# Schematic.net
KiCad netlist of a schematic drawn in Altium Designer
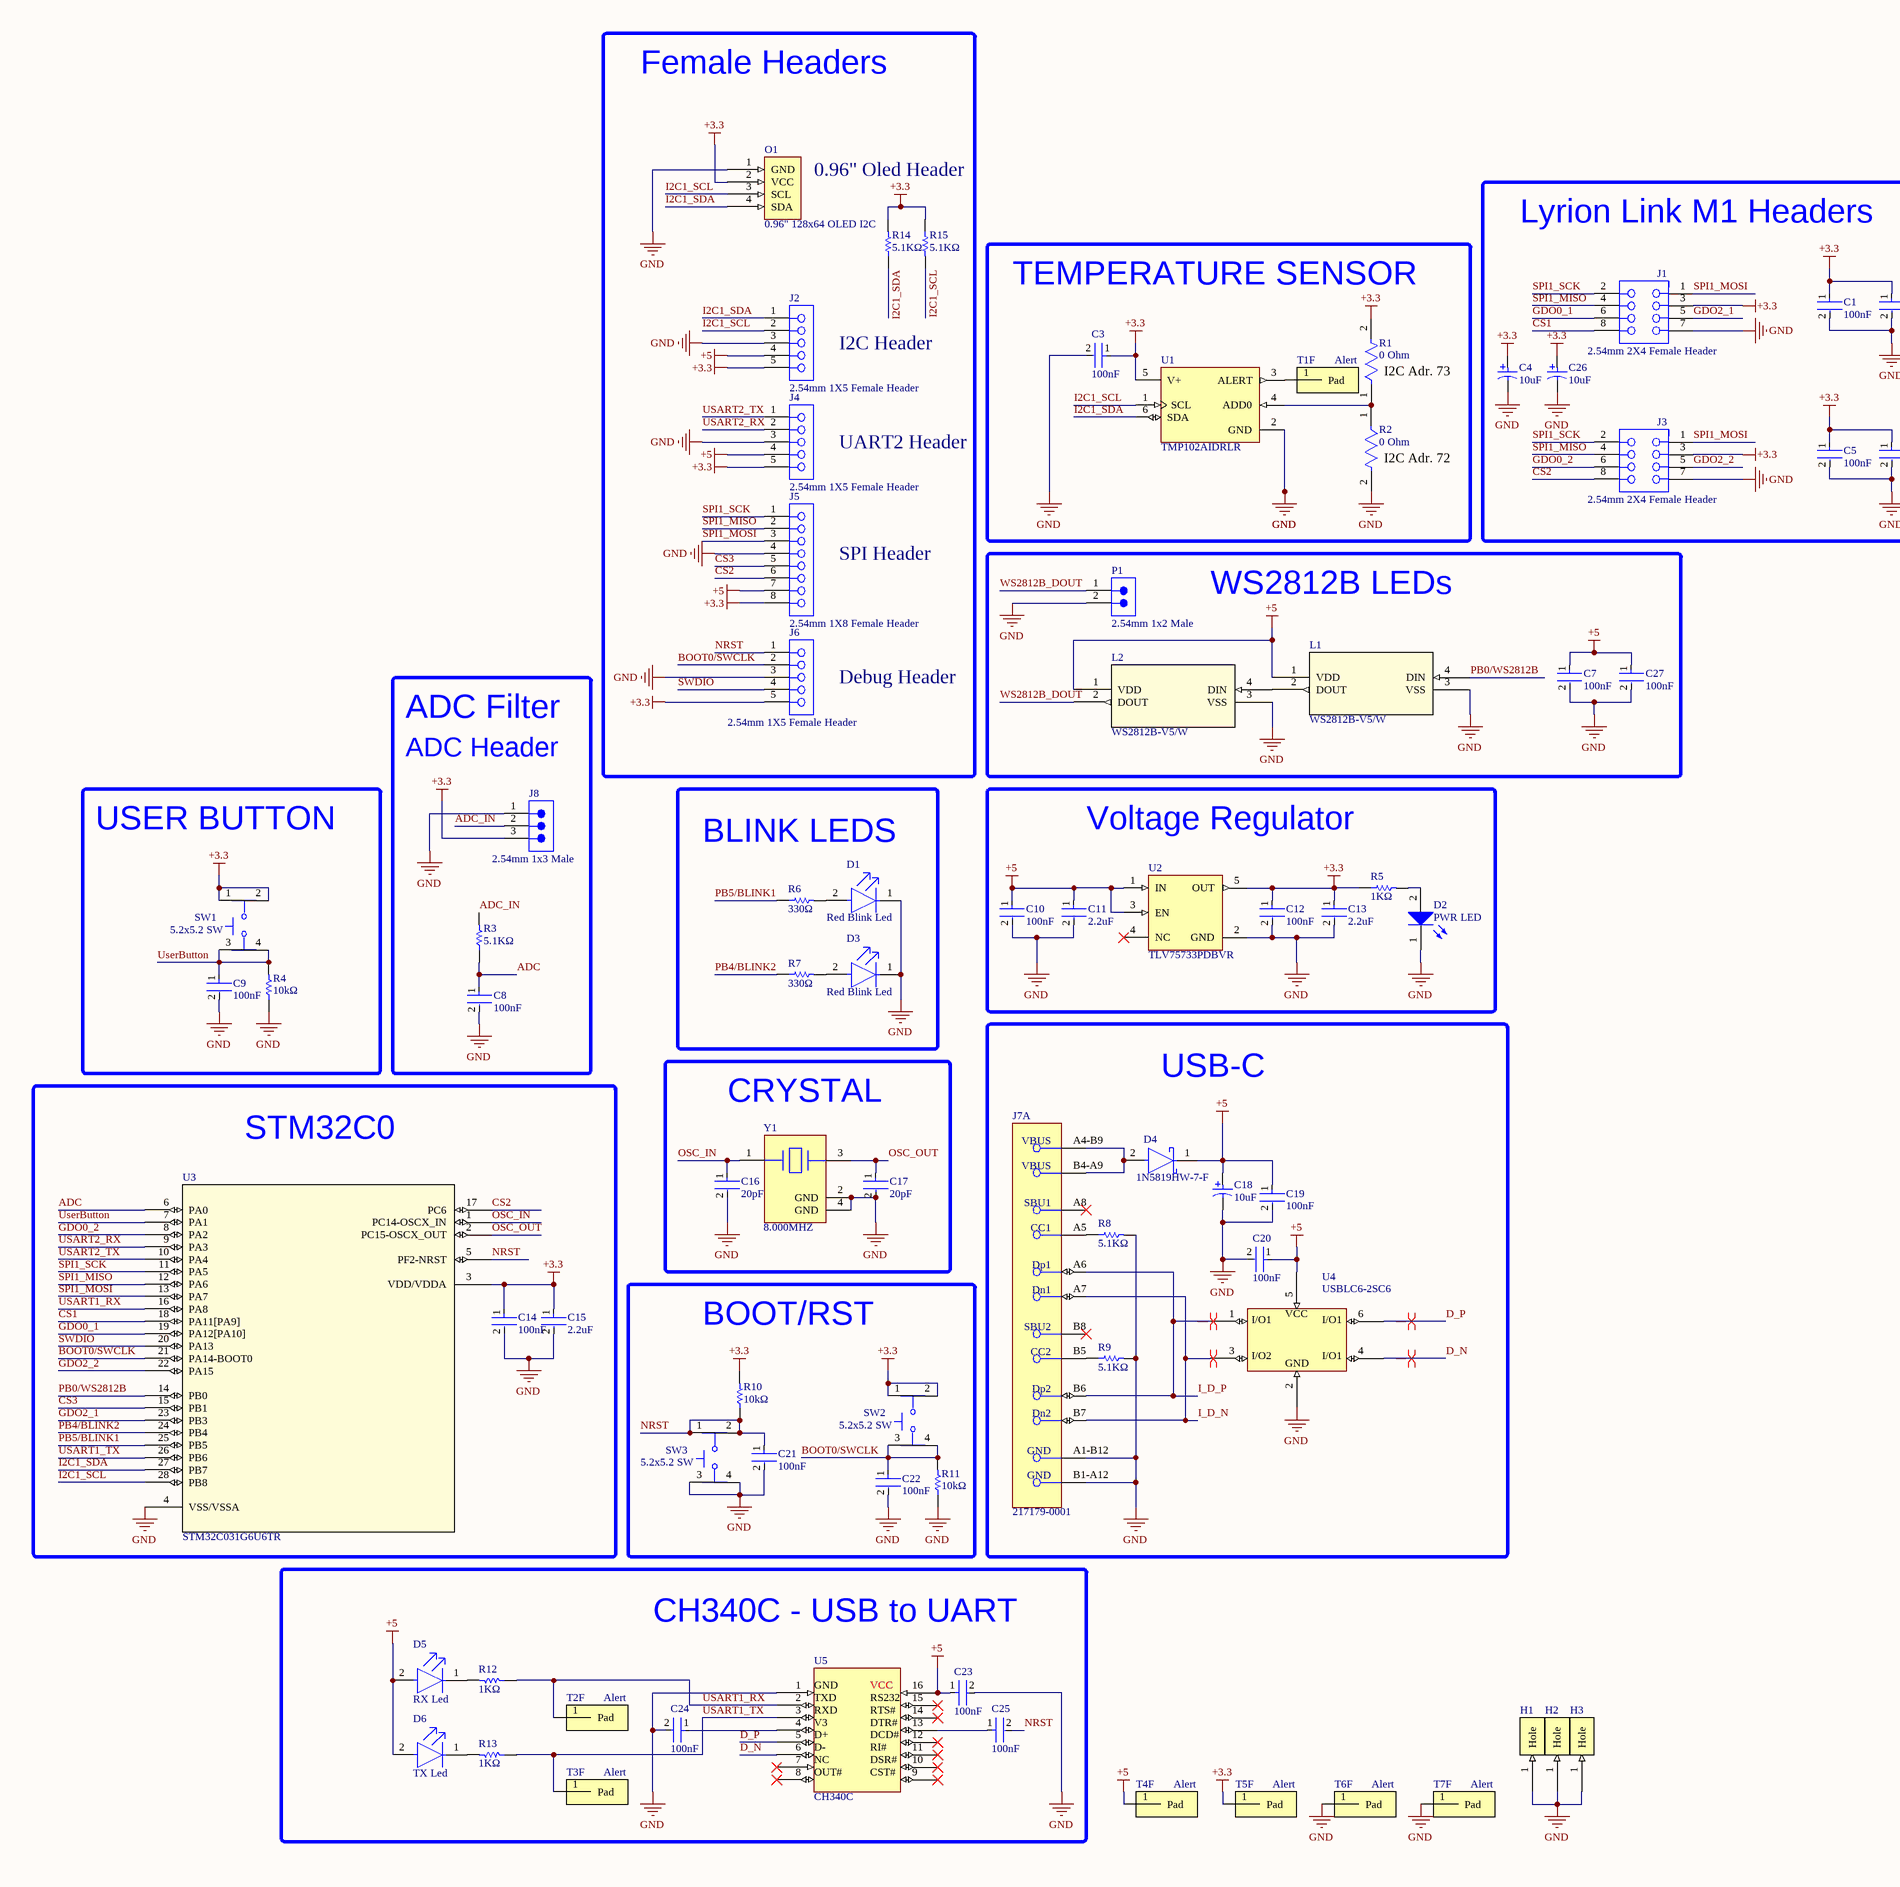
[diagram p0: Schematic.SchDoc, left]
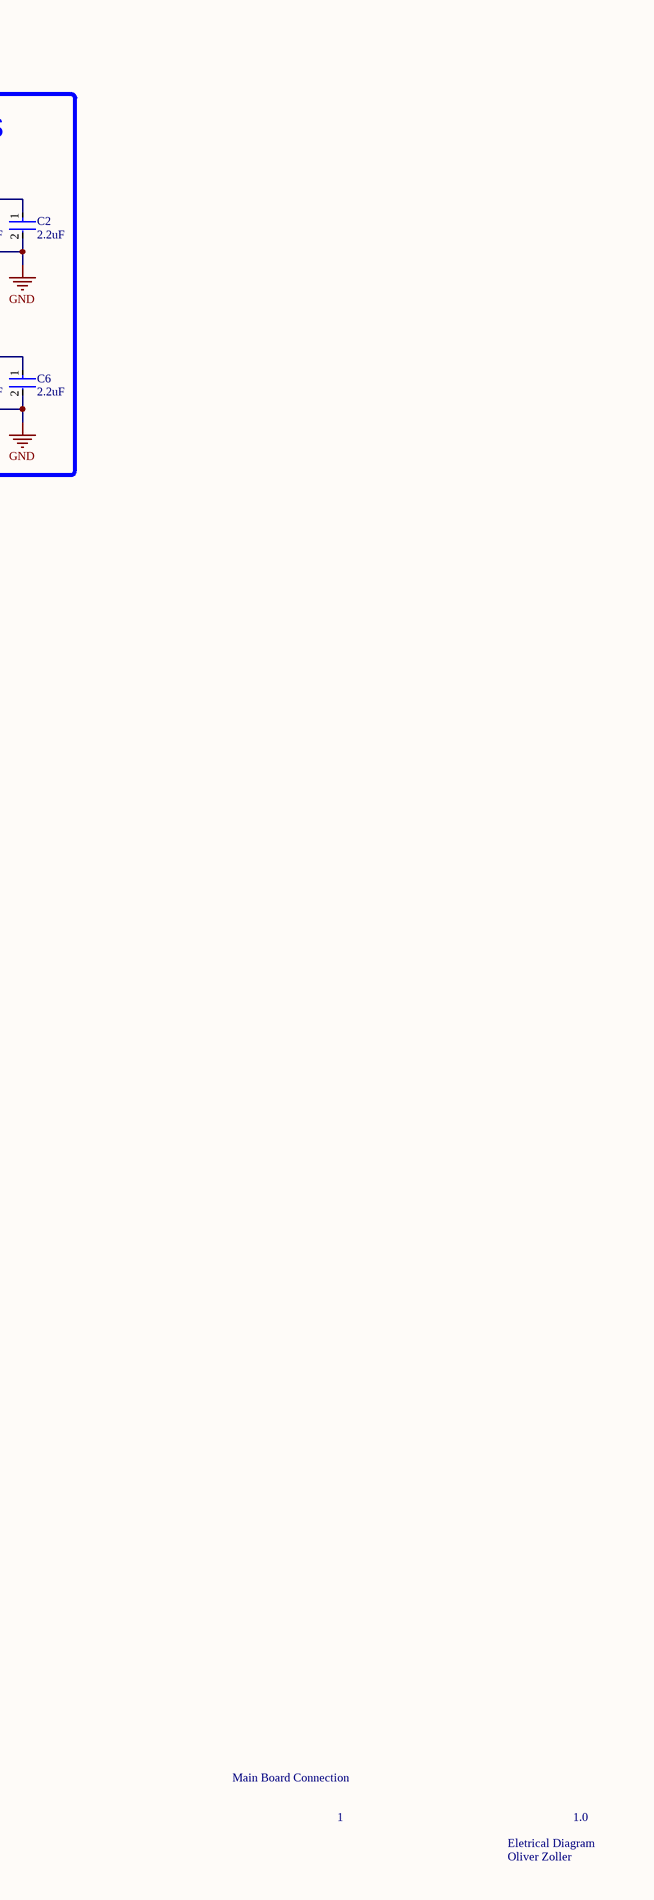
[diagram p1: Schematic.SchDoc, right]

(export (version "E")
  (design (tool "Eeschema 10.0.6"))
  (components
    (comp (ref "C1")
      (value "100nF")
      (footprint "FP-CC0603-DA-IPC_B")
      (description "100nF 0603 10% 50V")
      (fields (field (name "VOLTAGE") "50V") (field (name "TOLERANCE") "10%"))
      (libsource (lib "Main") (part "11868f565c42a9108669ba33697ecf6"))
    )
    (comp (ref "C2")
      (value "2.2uF")
      (footprint "FP-CL10-IPC_B")
      (description "2.2uF 0603 10% 16V")
      (fields (field (name "TOLERANCE") "10%") (field (name "VOLTAGE") "16V"))
      (libsource (lib "Main") (part "b4654b650e69147ec39a6b967a45e02"))
    )
    (comp (ref "C3")
      (value "100nF")
      (footprint "FP-CC0603-DA-IPC_B")
      (description "100nF 0603 10% 50V")
      (fields (field (name "VOLTAGE") "50V") (field (name "TOLERANCE") "10%"))
      (libsource (lib "Main") (part "11868f565c42a9108669ba33697ecf6"))
    )
    (comp (ref "C4")
      (value "10uF")
      (footprint "KEMT-A-3216-18-2_L")
      (description "10uF 0603 10%")
      (fields (field (name "VOLTAGE") "10V") (field (name "TOLERANCE") "10%"))
      (libsource (lib "Main") (part "CAP-P-2"))
    )
    (comp (ref "C5")
      (value "100nF")
      (footprint "FP-CC0603-DA-IPC_B")
      (description "100nF 0603 10% 50V")
      (fields (field (name "VOLTAGE") "50V") (field (name "TOLERANCE") "10%"))
      (libsource (lib "Main") (part "11868f565c42a9108669ba33697ecf6"))
    )
    (comp (ref "C6")
      (value "2.2uF")
      (footprint "FP-CL10-IPC_B")
      (description "2.2uF 0603 10% 16V")
      (fields (field (name "TOLERANCE") "10%") (field (name "VOLTAGE") "16V"))
      (libsource (lib "Main") (part "b4654b650e69147ec39a6b967a45e02"))
    )
    (comp (ref "C7")
      (value "100nF")
      (footprint "FP-CC0603-DA-IPC_B")
      (description "100nF 0603 10% 50V")
      (fields (field (name "VOLTAGE") "50V") (field (name "TOLERANCE") "10%"))
      (libsource (lib "Main") (part "11868f565c42a9108669ba33697ecf6"))
    )
    (comp (ref "C8")
      (value "100nF")
      (footprint "FP-CC0603-DA-IPC_B")
      (description "100nF 0603 10% 50V")
      (fields (field (name "VOLTAGE") "50V") (field (name "TOLERANCE") "10%"))
      (libsource (lib "Main") (part "11868f565c42a9108669ba33697ecf6"))
    )
    (comp (ref "C9")
      (value "100nF")
      (footprint "FP-CC0603-DA-IPC_B")
      (description "100nF 0603 10% 50V")
      (fields (field (name "VOLTAGE") "50V") (field (name "TOLERANCE") "10%"))
      (libsource (lib "Main") (part "11868f565c42a9108669ba33697ecf6"))
    )
    (comp (ref "C10")
      (value "100nF")
      (footprint "FP-CC0603-DA-IPC_B")
      (description "100nF 0603 10% 50V")
      (fields (field (name "VOLTAGE") "50V") (field (name "TOLERANCE") "10%"))
      (libsource (lib "Main") (part "11868f565c42a9108669ba33697ecf6"))
    )
    (comp (ref "C11")
      (value "2.2uF")
      (footprint "FP-CL10-IPC_B")
      (description "2.2uF 0603 10% 16V")
      (fields (field (name "TOLERANCE") "10%") (field (name "VOLTAGE") "16V"))
      (libsource (lib "Main") (part "b4654b650e69147ec39a6b967a45e02"))
    )
    (comp (ref "C12")
      (value "100nF")
      (footprint "FP-CC0603-DA-IPC_B")
      (description "100nF 0603 10% 50V")
      (fields (field (name "VOLTAGE") "50V") (field (name "TOLERANCE") "10%"))
      (libsource (lib "Main") (part "11868f565c42a9108669ba33697ecf6"))
    )
    (comp (ref "C13")
      (value "2.2uF")
      (footprint "FP-CL10-IPC_B")
      (description "2.2uF 0603 10% 16V")
      (fields (field (name "TOLERANCE") "10%") (field (name "VOLTAGE") "16V"))
      (libsource (lib "Main") (part "b4654b650e69147ec39a6b967a45e02"))
    )
    (comp (ref "C14")
      (value "100nF")
      (footprint "FP-CC0603-DA-IPC_B")
      (description "100nF 0603 10% 50V")
      (fields (field (name "VOLTAGE") "50V") (field (name "TOLERANCE") "10%"))
      (libsource (lib "Main") (part "11868f565c42a9108669ba33697ecf6"))
    )
    (comp (ref "C15")
      (value "2.2uF")
      (footprint "FP-CL10-IPC_B")
      (description "2.2uF 0603 10% 16V")
      (fields (field (name "TOLERANCE") "10%") (field (name "VOLTAGE") "16V"))
      (libsource (lib "Main") (part "b4654b650e69147ec39a6b967a45e02"))
    )
    (comp (ref "C16")
      (value "20pF")
      (footprint "FP-CC0603-0_9-IPC_A")
      (description "20pF 0603 5% 50V")
      (fields (field (name "TOLERANCE") "5%"))
      (libsource (lib "Main") (part "b4654b650e69147ec39a6b967a45e02"))
    )
    (comp (ref "C17")
      (value "20pF")
      (footprint "FP-CC0603-0_9-IPC_A")
      (description "20pF 0603 5% 50V")
      (fields (field (name "TOLERANCE") "5%"))
      (libsource (lib "Main") (part "b4654b650e69147ec39a6b967a45e02"))
    )
    (comp (ref "C18")
      (value "10uF")
      (footprint "KEMT-A-3216-18-2_L")
      (description "10uF 0603 10%")
      (fields (field (name "VOLTAGE") "10V") (field (name "TOLERANCE") "10%"))
      (libsource (lib "Main") (part "CAP-P-2"))
    )
    (comp (ref "C19")
      (value "100nF")
      (footprint "FP-CC0603-DA-IPC_B")
      (description "100nF 0603 10% 50V")
      (fields (field (name "VOLTAGE") "50V") (field (name "TOLERANCE") "10%"))
      (libsource (lib "Main") (part "11868f565c42a9108669ba33697ecf6"))
    )
    (comp (ref "C20")
      (value "100nF")
      (footprint "FP-CC0603-DA-IPC_B")
      (description "100nF 0603 10% 50V")
      (fields (field (name "VOLTAGE") "50V") (field (name "TOLERANCE") "10%"))
      (libsource (lib "Main") (part "11868f565c42a9108669ba33697ecf6"))
    )
    (comp (ref "C21")
      (value "100nF")
      (footprint "FP-CC0603-DA-IPC_B")
      (description "100nF 0603 10% 50V")
      (fields (field (name "VOLTAGE") "50V") (field (name "TOLERANCE") "10%"))
      (libsource (lib "Main") (part "11868f565c42a9108669ba33697ecf6"))
    )
    (comp (ref "C22")
      (value "100nF")
      (footprint "FP-CC0603-DA-IPC_B")
      (description "100nF 0603 10% 50V")
      (fields (field (name "VOLTAGE") "50V") (field (name "TOLERANCE") "10%"))
      (libsource (lib "Main") (part "11868f565c42a9108669ba33697ecf6"))
    )
    (comp (ref "C23")
      (value "100nF")
      (footprint "FP-CC0603-DA-IPC_B")
      (description "100nF 0603 10% 50V")
      (fields (field (name "VOLTAGE") "50V") (field (name "TOLERANCE") "10%"))
      (libsource (lib "Main") (part "11868f565c42a9108669ba33697ecf6"))
    )
    (comp (ref "C24")
      (value "100nF")
      (footprint "FP-CC0603-DA-IPC_B")
      (description "100nF 0603 10% 50V")
      (fields (field (name "VOLTAGE") "50V") (field (name "TOLERANCE") "10%"))
      (libsource (lib "Main") (part "11868f565c42a9108669ba33697ecf6"))
    )
    (comp (ref "C25")
      (value "100nF")
      (footprint "FP-CC0603-DA-IPC_B")
      (description "100nF 0603 10% 50V")
      (fields (field (name "VOLTAGE") "50V") (field (name "TOLERANCE") "10%"))
      (libsource (lib "Main") (part "11868f565c42a9108669ba33697ecf6"))
    )
    (comp (ref "C26")
      (value "10uF")
      (footprint "KEMT-A-3216-18-2_L")
      (description "10uF 0603 10%")
      (fields (field (name "VOLTAGE") "10V") (field (name "TOLERANCE") "10%"))
      (libsource (lib "Main") (part "CAP-P-2"))
    )
    (comp (ref "C27")
      (value "100nF")
      (footprint "FP-CC0603-DA-IPC_B")
      (description "100nF 0603 10% 50V")
      (fields (field (name "VOLTAGE") "50V") (field (name "TOLERANCE") "10%"))
      (libsource (lib "Main") (part "11868f565c42a9108669ba33697ecf6"))
    )
    (comp (ref "D1")
      (value "Red Blink Led")
      (footprint "FP-LTST-C190KRKT-MFG")
      (description "LED red 0603 wavelength 631nm light intensity 18~180mcd Front Mounting")
      (fields (field (name "TOLERANCE") "20%"))
      (libsource (lib "Main") (part "8706943c75ba83719d021d2fdc84c58"))
    )
    (comp (ref "D2")
      (value "PWR LED")
      (footprint "WL-SMCW_0603_150060xx75000")
      (description "WL-SMCW SMT Mono-Color Chip LED Waterclear")
      (libsource (lib "Main") (part "LED_Blue_2A-1K"))
    )
    (comp (ref "D3")
      (value "Red Blink Led")
      (footprint "FP-LTST-C190KRKT-MFG")
      (description "LED red 0603 wavelength 631nm light intensity 18~180mcd Front Mounting")
      (fields (field (name "TOLERANCE") "20%"))
      (libsource (lib "Main") (part "8706943c75ba83719d021d2fdc84c58"))
    )
    (comp (ref "D4")
      (value "1N5819HW-7-F")
      (footprint "FP-SOD123-IPC_C")
      (description "Schottky Diode SOD-123 40V 1A")
      (libsource (lib "Main") (part "1d6ec82d83fb6aee721767c19dac4b9"))
    )
    (comp (ref "D5")
      (value "RX Led")
      (footprint "FP-LTST-C190KRKT-MFG")
      (description "LED red 0603 wavelength 631nm light intensity 18~180mcd Front Mounting")
      (fields (field (name "TOLERANCE") "20%"))
      (libsource (lib "Main") (part "8706943c75ba83719d021d2fdc84c58"))
    )
    (comp (ref "D6")
      (value "TX Led")
      (footprint "FP-LTST-C190KRKT-MFG")
      (description "LED red 0603 wavelength 631nm light intensity 18~180mcd Front Mounting")
      (fields (field (name "TOLERANCE") "20%"))
      (libsource (lib "Main") (part "8706943c75ba83719d021d2fdc84c58"))
    )
    (comp (ref "H1")
      (value "M3 Mouting hole")
      (footprint "M3 Mouting hole-Footprint-1")
      (description "hole for M3 screw")
      (libsource (lib "Main") (part "M3 Mouting hole-Symbol-1"))
    )
    (comp (ref "H2")
      (value "M3 Mouting hole")
      (footprint "M3 Mouting hole-Footprint-1")
      (description "hole for M3 screw")
      (libsource (lib "Main") (part "M3 Mouting hole-Symbol-1"))
    )
    (comp (ref "H3")
      (value "M3 Mouting hole")
      (footprint "M3 Mouting hole-Footprint-1")
      (description "hole for M3 screw")
      (libsource (lib "Main") (part "M3 Mouting hole-Symbol-1"))
    )
    (comp (ref "J1")
      (value "2.54mm 2X4 Female Header")
      (footprint "61300821821")
      (description "8 Position Header Connector 0.100 (2.54mm) Through Hole Gold")
      (libsource (lib "Main") (part "Header_Female_2R_08P"))
    )
    (comp (ref "J2")
      (value "2.54mm 1X5 Female Header")
      (footprint "61300511821")
      (description "WR-PHD 2.54 mm Socket Header; 5 pins")
      (libsource (lib "Main") (part "Header_Female_1R_05P"))
    )
    (comp (ref "J3")
      (value "2.54mm 2X4 Female Header")
      (footprint "61300821821")
      (description "8 Position Header Connector 0.100 (2.54mm) Through Hole Gold")
      (libsource (lib "Main") (part "Header_Female_2R_08P"))
    )
    (comp (ref "J4")
      (value "2.54mm 1X5 Female Header")
      (footprint "61300511821")
      (description "WR-PHD 2.54 mm Socket Header; 5 pins")
      (libsource (lib "Main") (part "Header_Female_1R_05P"))
    )
    (comp (ref "J5")
      (value "2.54mm 1X8 Female Header")
      (footprint "61300811821")
      (description "Btb Conn, Rcpt, 8Pos, 1Row, 2.54Mm Rohs Compliant: Yes")
      (libsource (lib "Main") (part "Header_Female_1R_08P"))
    )
    (comp (ref "J6")
      (value "2.54mm 1X5 Female Header")
      (footprint "61300511821")
      (description "WR-PHD 2.54 mm Socket Header; 5 pins")
      (libsource (lib "Main") (part "Header_Female_1R_05P"))
    )
    (comp (ref "J7")
      (value "217179-0001")
      (footprint "FP-2171790001-MFG")
      (description "USB-C 16 pin")
      (libsource (lib "Main") (part "8b86497a633d14b3f74642136fc0ce6"))
    )
    (comp (ref "J8")
      (value "2.54mm 1x3 Male")
      (footprint "61300311121")
      (description "WR-PHD Straight Male, PCB Header, Through Hole, 1 Rows, 3 Contacts, 2.54mm Pitch")
      (libsource (lib "Main") (part "Header_Male_1R_03P"))
    )
    (comp (ref "L1")
      (value "WS2812B-V5/W")
      (footprint "WS2812B-V5_W-Footprint-1")
      (description "SMD5050-4P LED Addressable")
      (libsource (lib "Main") (part "WS2812B-V5_W-Symbol-1"))
    )
    (comp (ref "L2")
      (value "WS2812B-V5/W")
      (footprint "WS2812B-V5_W-Footprint-1")
      (description "SMD5050-4P LED Addressable")
      (libsource (lib "Main") (part "WS2812B-V5_W-Symbol-1"))
    )
    (comp (ref "O1")
      (value "0.96\" 128x64 OLED I2C")
      (footprint "0.96\" 128x64 OLED I2C-Footprint-1")
      (description "Display")
      (libsource (lib "Main") (part "0.96{dblquote} 128x64 OLED I2C-Symbol-1"))
    )
    (comp (ref "P1")
      (value "2.54mm 1x2 Male")
      (footprint "61300211121")
      (description "WR-PHD Straight Male, PCB Header, Through Hole, 1 Rows, 2 Contacts, 2.54mm Pitch")
      (libsource (lib "Main") (part "Header_Male_1R_02P"))
    )
    (comp (ref "R1")
      (value "0 Ohm")
      (footprint "FP-RC0603-MFG")
      (description "0 Ohm 0603")
      (fields (field (name "TOLERANCE") "1%"))
      (libsource (lib "Main") (part "1029c3af85768c4190bb7ad29bc67b5"))
    )
    (comp (ref "R2")
      (value "0 Ohm")
      (footprint "FP-RC0603-MFG")
      (description "0 Ohm 0603")
      (fields (field (name "TOLERANCE") "1%"))
      (libsource (lib "Main") (part "1029c3af85768c4190bb7ad29bc67b5"))
    )
    (comp (ref "R3")
      (value "5.1KΩ")
      (footprint "RESC1608X55X25ML10T15")
      (description "5.1KΩ 0603 1% 75V")
      (fields (field (name "TOLERANCE") "1%"))
      (libsource (lib "Main") (part "RES"))
    )
    (comp (ref "R4")
      (value "10kΩ")
      (footprint "RESC1609X50X30ML8T20")
      (description "10kΩ 0603 1% 75V")
      (fields (field (name "TOLERANCE") "1%"))
      (libsource (lib "Main") (part "RES-2"))
    )
    (comp (ref "R5")
      (value "1KΩ")
      (footprint "RESC1608X55X25ML10T15")
      (description "1KΩ 0603 1% 75V")
      (fields (field (name "TOLERANCE") "1%"))
      (libsource (lib "Main") (part "RES"))
    )
    (comp (ref "R6")
      (value "330Ω")
      (footprint "RESC1608X55X25LL10T15")
      (description "330Ω 0603 ±1% 75V")
      (fields (field (name "TOLERANCE") "1%"))
      (libsource (lib "Main") (part "RES-2"))
    )
    (comp (ref "R7")
      (value "330Ω")
      (footprint "RESC1608X55X25LL10T15")
      (description "330Ω 0603 ±1% 75V")
      (fields (field (name "TOLERANCE") "1%"))
      (libsource (lib "Main") (part "RES-2"))
    )
    (comp (ref "R8")
      (value "5.1KΩ")
      (footprint "RESC1608X55X25ML10T15")
      (description "5.1KΩ 0603 1% 75V")
      (fields (field (name "TOLERANCE") "1%"))
      (libsource (lib "Main") (part "RES"))
    )
    (comp (ref "R9")
      (value "5.1KΩ")
      (footprint "RESC1608X55X25ML10T15")
      (description "5.1KΩ 0603 1% 75V")
      (fields (field (name "TOLERANCE") "1%"))
      (libsource (lib "Main") (part "RES"))
    )
    (comp (ref "R10")
      (value "10kΩ")
      (footprint "RESC1609X50X30ML8T20")
      (description "10kΩ 0603 1% 75V")
      (fields (field (name "TOLERANCE") "1%"))
      (libsource (lib "Main") (part "RES-2"))
    )
    (comp (ref "R11")
      (value "10kΩ")
      (footprint "RESC1609X50X30ML8T20")
      (description "10kΩ 0603 1% 75V")
      (fields (field (name "TOLERANCE") "1%"))
      (libsource (lib "Main") (part "RES-2"))
    )
    (comp (ref "R12")
      (value "1KΩ")
      (footprint "RESC1608X55X25ML10T15")
      (description "1KΩ 0603 1% 75V")
      (fields (field (name "TOLERANCE") "1%"))
      (libsource (lib "Main") (part "RES"))
    )
    (comp (ref "R13")
      (value "1KΩ")
      (footprint "RESC1608X55X25ML10T15")
      (description "1KΩ 0603 1% 75V")
      (fields (field (name "TOLERANCE") "1%"))
      (libsource (lib "Main") (part "RES"))
    )
    (comp (ref "R14")
      (value "5.1KΩ")
      (footprint "RESC1608X55X25ML10T15")
      (description "5.1KΩ 0603 1% 75V")
      (fields (field (name "TOLERANCE") "1%"))
      (libsource (lib "Main") (part "RES"))
    )
    (comp (ref "R15")
      (value "5.1KΩ")
      (footprint "RESC1608X55X25ML10T15")
      (description "5.1KΩ 0603 1% 75V")
      (fields (field (name "TOLERANCE") "1%"))
      (libsource (lib "Main") (part "RES"))
    )
    (comp (ref "SW1")
      (value "5.2x5.2 SW")
      (footprint "FP-TL3342F450QG-MFG")
      (description "Tactile Switch  5.2x5.2 Round Button")
      (libsource (lib "Main") (part "515be15a89bd7fba83aa4975ec48af4"))
    )
    (comp (ref "SW2")
      (value "5.2x5.2 SW")
      (footprint "FP-TL3342F450QG-MFG")
      (description "Tactile Switch  5.2x5.2 Round Button")
      (libsource (lib "Main") (part "515be15a89bd7fba83aa4975ec48af4"))
    )
    (comp (ref "SW3")
      (value "5.2x5.2 SW")
      (footprint "FP-TL3342F450QG-MFG")
      (description "Tactile Switch  5.2x5.2 Round Button")
      (libsource (lib "Main") (part "515be15a89bd7fba83aa4975ec48af4"))
    )
    (comp (ref "T1")
      (value "Alert")
      (footprint "Test Pad-Footprint-1")
      (description "Pad for probing - soldering")
      (libsource (lib "Main") (part "Test Pad-Symbol-1"))
    )
    (comp (ref "T2")
      (value "Alert")
      (footprint "Test Pad-Footprint-1")
      (description "Pad for probing - soldering")
      (libsource (lib "Main") (part "Test Pad-Symbol-1"))
    )
    (comp (ref "T3")
      (value "Alert")
      (footprint "Test Pad-Footprint-1")
      (description "Pad for probing - soldering")
      (libsource (lib "Main") (part "Test Pad-Symbol-1"))
    )
    (comp (ref "T4")
      (value "Alert")
      (footprint "Test Pad-Footprint-1")
      (description "Pad for probing - soldering")
      (libsource (lib "Main") (part "Test Pad-Symbol-1"))
    )
    (comp (ref "T5")
      (value "Alert")
      (footprint "Test Pad-Footprint-1")
      (description "Pad for probing - soldering")
      (libsource (lib "Main") (part "Test Pad-Symbol-1"))
    )
    (comp (ref "T6")
      (value "Alert")
      (footprint "Test Pad-Footprint-1")
      (description "Pad for probing - soldering")
      (libsource (lib "Main") (part "Test Pad-Symbol-1"))
    )
    (comp (ref "T7")
      (value "Alert")
      (footprint "Test Pad-Footprint-1")
      (description "Pad for probing - soldering")
      (libsource (lib "Main") (part "Test Pad-Symbol-1"))
    )
    (comp (ref "U1")
      (value "TMP102AIDRLR")
      (footprint "FP-DRL0006A-MFG")
      (description "Digital Temperature Sensor -40℃~+125℃ I2C ±0.5℃ 1.4V~3.6V SOT-563 Analog and Digital Outpu")
      (libsource (lib "Main") (part "0dc0cc90889c8b3dc03258d40cf2b82"))
    )
    (comp (ref "U2")
      (value "TLV75733PDBVR")
      (footprint "FP-DBV0005A-MFG")
      (description "LDO 3.3V 1A 5-SOT-23")
      (libsource (lib "Main") (part "0cbbc1df71e5372cce39b1d408f1f92"))
    )
    (comp (ref "U3")
      (value "STM32C031G6U6TR")
      (footprint "UFQFPN-28_STM")
      (fields (field (name "COPYRIGHT") "Copyright (C) 2026 Ultra Librarian. All rights reserved."))
      (libsource (lib "Main") (part "STM32C031G6U6TR"))
    )
    (comp (ref "U4")
      (value "USBLC6-2SC6")
      (footprint "STM-SOT23-6L_V")
      (description "USB ESD SOT-23-6 and Surge Protection (TVS/ESD)")
      (libsource (lib "Main") (part "USBLC6-2SC6-Symbol-1"))
    )
    (comp (ref "U5")
      (value "CH340C")
      (footprint "CH340C-Footprint-1")
      (description "USB to Serial Port chip Transceiver 2Mbps USB 2.0 SOP-16 Interface Controllers RoHS")
      (fields
        (field (name "SOURCE") "https://www.lcsc.com/product-detail/C84681.html?spm=wm.gwc.xh.55.cbm___wm.sy.ssl.gwc&lcsc_vid=QQVdUgADR1gPUVVXRVZXVQJRRVdbBFZWEwdaVgBXQwAxVlNRTlBZUFFRRlZYUTtW")
      )
      (libsource (lib "Main") (part "CH340C"))
    )
    (comp (ref "Y1")
      (value "8.000MHZ")
      (footprint "FP-ABM3B-MFG")
      (description "Crystal 8MHz ±10ppm SMD5032-4P 20pF")
      (fields (field (name "TOLERANCE") "0.002%"))
      (libsource (lib "Main") (part "48e526d86b7f2615d98721063c72f49"))
    )
  )
  (nets
    (net (code "1") (name "+3.3") (class "Default")
      (node (ref "C1") (pin "1") (pinfunction "1_1") (pintype "passive"))
      (node (ref "C12") (pin "1") (pinfunction "1_1") (pintype "passive"))
      (node (ref "C13") (pin "1") (pinfunction "1_1") (pintype "passive"))
      (node (ref "C14") (pin "1") (pinfunction "1_1") (pintype "passive"))
      (node (ref "C15") (pin "1") (pinfunction "1_1") (pintype "passive"))
      (node (ref "C2") (pin "1") (pinfunction "1_1") (pintype "passive"))
      (node (ref "C26") (pin "1") (pinfunction "1_1") (pintype "passive"))
      (node (ref "C3") (pin "1") (pinfunction "1_1") (pintype "passive"))
      (node (ref "C4") (pin "1") (pinfunction "1_1") (pintype "passive"))
      (node (ref "C5") (pin "1") (pinfunction "1_1") (pintype "passive"))
      (node (ref "C6") (pin "1") (pinfunction "1_1") (pintype "passive"))
      (node (ref "J1") (pin "3") (pinfunction "3_3") (pintype "passive"))
      (node (ref "J2") (pin "5") (pinfunction "5_5") (pintype "passive"))
      (node (ref "J3") (pin "3") (pinfunction "3_3") (pintype "passive"))
      (node (ref "J4") (pin "5") (pinfunction "5_5") (pintype "passive"))
      (node (ref "J5") (pin "8") (pinfunction "8_8") (pintype "passive"))
      (node (ref "J6") (pin "5") (pinfunction "5_5") (pintype "passive"))
      (node (ref "J8") (pin "3") (pinfunction "3_3") (pintype "passive"))
      (node (ref "O1") (pin "2") (pinfunction "VCC_2") (pintype "input"))
      (node (ref "R1") (pin "2") (pinfunction "2_2") (pintype "passive"))
      (node (ref "R10") (pin "2") (pinfunction "2_2") (pintype "passive"))
      (node (ref "R14") (pin "2") (pinfunction "2_2") (pintype "passive"))
      (node (ref "R15") (pin "1") (pinfunction "1_1") (pintype "passive"))
      (node (ref "R5") (pin "1") (pinfunction "1_1") (pintype "passive"))
      (node (ref "SW1") (pin "1") (pinfunction "1_1") (pintype "passive"))
      (node (ref "SW1") (pin "2") (pinfunction "2_2") (pintype "passive"))
      (node (ref "SW2") (pin "1") (pinfunction "1_1") (pintype "passive"))
      (node (ref "SW2") (pin "2") (pinfunction "2_2") (pintype "passive"))
      (node (ref "T5") (pin "1") (pinfunction "Pad_1") (pintype "passive"))
      (node (ref "U1") (pin "5") (pinfunction "V+_5") (pintype "power_in"))
      (node (ref "U2") (pin "5") (pinfunction "OUT_5") (pintype "output"))
      (node (ref "U3") (pin "3") (pinfunction "VDD/VDDA_3") (pintype "power_in"))
    )
    (net (code "2") (name "+5") (class "Default")
      (node (ref "C10") (pin "1") (pinfunction "1_1") (pintype "passive"))
      (node (ref "C11") (pin "1") (pinfunction "1_1") (pintype "passive"))
      (node (ref "C18") (pin "1") (pinfunction "1_1") (pintype "passive"))
      (node (ref "C19") (pin "1") (pinfunction "1_1") (pintype "passive"))
      (node (ref "C20") (pin "1") (pinfunction "1_1") (pintype "passive"))
      (node (ref "C23") (pin "1") (pinfunction "1_1") (pintype "passive"))
      (node (ref "C27") (pin "1") (pinfunction "1_1") (pintype "passive"))
      (node (ref "C7") (pin "1") (pinfunction "1_1") (pintype "passive"))
      (node (ref "D4") (pin "1") (pinfunction "C_1") (pintype "passive"))
      (node (ref "D5") (pin "2") (pinfunction "A_2") (pintype "passive"))
      (node (ref "D6") (pin "2") (pinfunction "A_2") (pintype "passive"))
      (node (ref "J2") (pin "4") (pinfunction "4_4") (pintype "passive"))
      (node (ref "J4") (pin "4") (pinfunction "4_4") (pintype "passive"))
      (node (ref "J5") (pin "7") (pinfunction "7_7") (pintype "passive"))
      (node (ref "L1") (pin "1") (pinfunction "VDD_1") (pintype "power_in"))
      (node (ref "L2") (pin "1") (pinfunction "VDD_1") (pintype "power_in"))
      (node (ref "T4") (pin "1") (pinfunction "Pad_1") (pintype "passive"))
      (node (ref "U2") (pin "1") (pinfunction "IN_1") (pintype "input"))
      (node (ref "U2") (pin "3") (pinfunction "EN_3") (pintype "input"))
      (node (ref "U4") (pin "5") (pintype "input"))
      (node (ref "U5") (pin "16") (pintype "input"))
    )
    (net (code "3") (name "/ADC") (class "Default")
      (node (ref "C8") (pin "1") (pinfunction "1_1") (pintype "passive"))
      (node (ref "R3") (pin "1") (pinfunction "1_1") (pintype "passive"))
      (node (ref "U3") (pin "6") (pinfunction "PA0_6") (pintype "bidirectional"))
    )
    (net (code "4") (name "/ADC_IN") (class "Default")
      (node (ref "J8") (pin "2") (pinfunction "2_2") (pintype "passive"))
      (node (ref "R3") (pin "2") (pinfunction "2_2") (pintype "passive"))
    )
    (net (code "5") (name "/BOOT0{slash}SWCLK") (class "Default")
      (node (ref "C22") (pin "1") (pinfunction "1_1") (pintype "passive"))
      (node (ref "J6") (pin "2") (pinfunction "2_2") (pintype "passive"))
      (node (ref "R11") (pin "2") (pinfunction "2_2") (pintype "passive"))
      (node (ref "SW2") (pin "3") (pinfunction "3_3") (pintype "passive"))
      (node (ref "SW2") (pin "4") (pinfunction "4_4") (pintype "passive"))
      (node (ref "U3") (pin "21") (pinfunction "PA14-BOOT0_21") (pintype "bidirectional"))
    )
    (net (code "6") (name "/CS1") (class "Default")
      (node (ref "J1") (pin "8") (pinfunction "8_8") (pintype "passive"))
      (node (ref "U3") (pin "18") (pinfunction "PA11[PA9]_18") (pintype "bidirectional"))
    )
    (net (code "7") (name "/CS2") (class "Default")
      (node (ref "J3") (pin "8") (pinfunction "8_8") (pintype "passive"))
      (node (ref "J5") (pin "6") (pinfunction "6_6") (pintype "passive"))
      (node (ref "U3") (pin "17") (pinfunction "PC6_17") (pintype "bidirectional"))
    )
    (net (code "8") (name "/CS3") (class "Default")
      (node (ref "J5") (pin "5") (pinfunction "5_5") (pintype "passive"))
      (node (ref "U3") (pin "15") (pinfunction "PB1_15") (pintype "bidirectional"))
    )
    (net (code "9") (name "/D_N") (class "Default")
      (node (ref "U4") (pin "4") (pintype "bidirectional"))
      (node (ref "U5") (pin "6") (pintype "bidirectional"))
    )
    (net (code "10") (name "/D_P") (class "Default")
      (node (ref "U4") (pin "6") (pintype "bidirectional"))
      (node (ref "U5") (pin "5") (pintype "bidirectional"))
    )
    (net (code "11") (name "/GDO0_1") (class "Default")
      (node (ref "J1") (pin "6") (pinfunction "6_6") (pintype "passive"))
      (node (ref "U3") (pin "19") (pinfunction "PA12[PA10]_19") (pintype "bidirectional"))
    )
    (net (code "12") (name "/GDO0_2") (class "Default")
      (node (ref "J3") (pin "6") (pinfunction "6_6") (pintype "passive"))
      (node (ref "U3") (pin "8") (pinfunction "PA2_8") (pintype "bidirectional"))
    )
    (net (code "13") (name "/GDO2_1") (class "Default")
      (node (ref "J1") (pin "5") (pinfunction "5_5") (pintype "passive"))
      (node (ref "U3") (pin "23") (pinfunction "PB3_23") (pintype "bidirectional"))
    )
    (net (code "14") (name "/GDO2_2") (class "Default")
      (node (ref "J3") (pin "5") (pinfunction "5_5") (pintype "passive"))
      (node (ref "U3") (pin "22") (pinfunction "PA15_22") (pintype "bidirectional"))
    )
    (net (code "15") (name "/I2C1_SCL") (class "Default")
      (node (ref "J2") (pin "2") (pinfunction "2_2") (pintype "passive"))
      (node (ref "O1") (pin "3") (pinfunction "SCL_3") (pintype "input"))
      (node (ref "R15") (pin "2") (pinfunction "2_2") (pintype "passive"))
      (node (ref "U1") (pin "1") (pinfunction "SCL_1") (pintype "input"))
      (node (ref "U3") (pin "28") (pinfunction "PB8_28") (pintype "bidirectional"))
    )
    (net (code "16") (name "/I2C1_SDA") (class "Default")
      (node (ref "J2") (pin "1") (pinfunction "1_1") (pintype "passive"))
      (node (ref "O1") (pin "4") (pinfunction "SDA_4") (pintype "input"))
      (node (ref "R14") (pin "1") (pinfunction "1_1") (pintype "passive"))
      (node (ref "U1") (pin "6") (pinfunction "SDA_6") (pintype "bidirectional"))
      (node (ref "U3") (pin "27") (pinfunction "PB7_27") (pintype "bidirectional"))
    )
    (net (code "17") (name "/I_D_N") (class "Default")
      (node (ref "J7") (pin "A7") (pinfunction "Dn1_A7") (pintype "bidirectional"))
      (node (ref "J7") (pin "B7") (pinfunction "Dn2_B7") (pintype "bidirectional"))
      (node (ref "U4") (pin "3") (pintype "bidirectional"))
    )
    (net (code "18") (name "/I_D_P") (class "Default")
      (node (ref "J7") (pin "A6") (pinfunction "Dp1_A6") (pintype "bidirectional"))
      (node (ref "J7") (pin "B6") (pinfunction "Dp2_B6") (pintype "bidirectional"))
      (node (ref "U4") (pin "1") (pintype "bidirectional"))
    )
    (net (code "19") (name "/NRST") (class "Default")
      (node (ref "C21") (pin "1") (pinfunction "1_1") (pintype "passive"))
      (node (ref "C25") (pin "2") (pinfunction "2_2") (pintype "passive"))
      (node (ref "J6") (pin "1") (pinfunction "1_1") (pintype "passive"))
      (node (ref "R10") (pin "1") (pinfunction "1_1") (pintype "passive"))
      (node (ref "SW3") (pin "1") (pinfunction "1_1") (pintype "passive"))
      (node (ref "SW3") (pin "2") (pinfunction "2_2") (pintype "passive"))
      (node (ref "U3") (pin "5") (pinfunction "PF2-NRST_5") (pintype "bidirectional"))
    )
    (net (code "20") (name "/OSC_IN") (class "Default")
      (node (ref "C16") (pin "1") (pinfunction "1_1") (pintype "passive"))
      (node (ref "U3") (pin "1") (pinfunction "PC14-OSCX_IN_1") (pintype "bidirectional"))
      (node (ref "Y1") (pin "1") (pinfunction "1_1") (pintype "passive"))
    )
    (net (code "21") (name "/OSC_OUT") (class "Default")
      (node (ref "C17") (pin "1") (pinfunction "1_1") (pintype "passive"))
      (node (ref "U3") (pin "2") (pinfunction "PC15-OSCX_OUT_2") (pintype "bidirectional"))
      (node (ref "Y1") (pin "3") (pinfunction "3_3") (pintype "passive"))
    )
    (net (code "22") (name "/PB0{slash}WS2812B") (class "Default")
      (node (ref "L1") (pin "4") (pinfunction "DIN_4") (pintype "input"))
      (node (ref "U3") (pin "14") (pinfunction "PB0_14") (pintype "bidirectional"))
    )
    (net (code "23") (name "/PB4{slash}BLINK2") (class "Default")
      (node (ref "R7") (pin "1") (pinfunction "1_1") (pintype "passive"))
      (node (ref "U3") (pin "24") (pinfunction "PB4_24") (pintype "bidirectional"))
    )
    (net (code "24") (name "/PB5{slash}BLINK1") (class "Default")
      (node (ref "R6") (pin "1") (pinfunction "1_1") (pintype "passive"))
      (node (ref "U3") (pin "25") (pinfunction "PB5_25") (pintype "bidirectional"))
    )
    (net (code "25") (name "/SPI1_MISO") (class "Default")
      (node (ref "J1") (pin "4") (pinfunction "4_4") (pintype "passive"))
      (node (ref "J3") (pin "4") (pinfunction "4_4") (pintype "passive"))
      (node (ref "J5") (pin "2") (pinfunction "2_2") (pintype "passive"))
      (node (ref "U3") (pin "12") (pinfunction "PA6_12") (pintype "bidirectional"))
    )
    (net (code "26") (name "/SPI1_MOSI") (class "Default")
      (node (ref "J1") (pin "1") (pinfunction "1_1") (pintype "passive"))
      (node (ref "J3") (pin "1") (pinfunction "1_1") (pintype "passive"))
      (node (ref "J5") (pin "3") (pinfunction "3_3") (pintype "passive"))
      (node (ref "U3") (pin "13") (pinfunction "PA7_13") (pintype "bidirectional"))
    )
    (net (code "27") (name "/SPI1_SCK") (class "Default")
      (node (ref "J1") (pin "2") (pinfunction "2_2") (pintype "passive"))
      (node (ref "J3") (pin "2") (pinfunction "2_2") (pintype "passive"))
      (node (ref "J5") (pin "1") (pinfunction "1_1") (pintype "passive"))
      (node (ref "U3") (pin "11") (pinfunction "PA5_11") (pintype "bidirectional"))
    )
    (net (code "28") (name "/SWDIO") (class "Default")
      (node (ref "J6") (pin "4") (pinfunction "4_4") (pintype "passive"))
      (node (ref "U3") (pin "20") (pinfunction "PA13_20") (pintype "bidirectional"))
    )
    (net (code "29") (name "/USART1_RX") (class "Default")
      (node (ref "R12") (pin "1") (pinfunction "1_1") (pintype "passive"))
      (node (ref "T2") (pin "1") (pinfunction "Pad_1") (pintype "passive"))
      (node (ref "U3") (pin "16") (pinfunction "PA8_16") (pintype "bidirectional"))
      (node (ref "U5") (pin "2") (pintype "bidirectional"))
    )
    (net (code "30") (name "/USART1_TX") (class "Default")
      (node (ref "R13") (pin "1") (pinfunction "1_1") (pintype "passive"))
      (node (ref "T3") (pin "1") (pinfunction "Pad_1") (pintype "passive"))
      (node (ref "U3") (pin "26") (pinfunction "PB6_26") (pintype "bidirectional"))
      (node (ref "U5") (pin "3") (pintype "bidirectional"))
    )
    (net (code "31") (name "/USART2_RX") (class "Default")
      (node (ref "J4") (pin "2") (pinfunction "2_2") (pintype "passive"))
      (node (ref "U3") (pin "9") (pinfunction "PA3_9") (pintype "bidirectional"))
    )
    (net (code "32") (name "/USART2_TX") (class "Default")
      (node (ref "J4") (pin "1") (pinfunction "1_1") (pintype "passive"))
      (node (ref "U3") (pin "10") (pinfunction "PA4_10") (pintype "bidirectional"))
    )
    (net (code "33") (name "/UserButton") (class "Default")
      (node (ref "C9") (pin "1") (pinfunction "1_1") (pintype "passive"))
      (node (ref "R4") (pin "2") (pinfunction "2_2") (pintype "passive"))
      (node (ref "SW1") (pin "3") (pinfunction "3_3") (pintype "passive"))
      (node (ref "SW1") (pin "4") (pinfunction "4_4") (pintype "passive"))
      (node (ref "U3") (pin "7") (pinfunction "PA1_7") (pintype "bidirectional"))
    )
    (net (code "34") (name "/WS2812B_DOUT") (class "Default")
      (node (ref "L2") (pin "2") (pinfunction "DOUT_2") (pintype "output"))
      (node (ref "P1") (pin "1") (pinfunction "1_1") (pintype "passive"))
    )
    (net (code "35") (name "GND") (class "Default")
      (node (ref "C1") (pin "2") (pinfunction "2_2") (pintype "passive"))
      (node (ref "C10") (pin "2") (pinfunction "2_2") (pintype "passive"))
      (node (ref "C11") (pin "2") (pinfunction "2_2") (pintype "passive"))
      (node (ref "C12") (pin "2") (pinfunction "2_2") (pintype "passive"))
      (node (ref "C13") (pin "2") (pinfunction "2_2") (pintype "passive"))
      (node (ref "C14") (pin "2") (pinfunction "2_2") (pintype "passive"))
      (node (ref "C15") (pin "2") (pinfunction "2_2") (pintype "passive"))
      (node (ref "C16") (pin "2") (pinfunction "2_2") (pintype "passive"))
      (node (ref "C17") (pin "2") (pinfunction "2_2") (pintype "passive"))
      (node (ref "C18") (pin "2") (pinfunction "2_2") (pintype "passive"))
      (node (ref "C19") (pin "2") (pinfunction "2_2") (pintype "passive"))
      (node (ref "C2") (pin "2") (pinfunction "2_2") (pintype "passive"))
      (node (ref "C20") (pin "2") (pinfunction "2_2") (pintype "passive"))
      (node (ref "C21") (pin "2") (pinfunction "2_2") (pintype "passive"))
      (node (ref "C22") (pin "2") (pinfunction "2_2") (pintype "passive"))
      (node (ref "C23") (pin "2") (pinfunction "2_2") (pintype "passive"))
      (node (ref "C24") (pin "2") (pinfunction "2_2") (pintype "passive"))
      (node (ref "C26") (pin "2") (pinfunction "2_2") (pintype "passive"))
      (node (ref "C27") (pin "2") (pinfunction "2_2") (pintype "passive"))
      (node (ref "C3") (pin "2") (pinfunction "2_2") (pintype "passive"))
      (node (ref "C4") (pin "2") (pinfunction "2_2") (pintype "passive"))
      (node (ref "C5") (pin "2") (pinfunction "2_2") (pintype "passive"))
      (node (ref "C6") (pin "2") (pinfunction "2_2") (pintype "passive"))
      (node (ref "C7") (pin "2") (pinfunction "2_2") (pintype "passive"))
      (node (ref "C8") (pin "2") (pinfunction "2_2") (pintype "passive"))
      (node (ref "C9") (pin "2") (pinfunction "2_2") (pintype "passive"))
      (node (ref "D1") (pin "1") (pinfunction "C_1") (pintype "passive"))
      (node (ref "D2") (pin "1") (pinfunction "K_1") (pintype "passive"))
      (node (ref "D3") (pin "1") (pinfunction "C_1") (pintype "passive"))
      (node (ref "H1") (pin "1") (pinfunction "Hole_1") (pintype "input"))
      (node (ref "H2") (pin "1") (pinfunction "Hole_1") (pintype "input"))
      (node (ref "H3") (pin "1") (pinfunction "Hole_1") (pintype "input"))
      (node (ref "J1") (pin "7") (pinfunction "7_7") (pintype "passive"))
      (node (ref "J2") (pin "3") (pinfunction "3_3") (pintype "passive"))
      (node (ref "J3") (pin "7") (pinfunction "7_7") (pintype "passive"))
      (node (ref "J4") (pin "3") (pinfunction "3_3") (pintype "passive"))
      (node (ref "J5") (pin "4") (pinfunction "4_4") (pintype "passive"))
      (node (ref "J6") (pin "3") (pinfunction "3_3") (pintype "passive"))
      (node (ref "J7") (pin "A1-B12") (pinfunction "GND_A1-B12") (pintype "power_in"))
      (node (ref "J7") (pin "B1-A12") (pinfunction "GND_B1-A12") (pintype "power_in"))
      (node (ref "J8") (pin "1") (pinfunction "1_1") (pintype "passive"))
      (node (ref "L1") (pin "3") (pinfunction "VSS_3") (pintype "power_in"))
      (node (ref "L2") (pin "3") (pinfunction "VSS_3") (pintype "power_in"))
      (node (ref "O1") (pin "1") (pinfunction "GND_1") (pintype "input"))
      (node (ref "P1") (pin "2") (pinfunction "2_2") (pintype "passive"))
      (node (ref "R11") (pin "1") (pinfunction "1_1") (pintype "passive"))
      (node (ref "R2") (pin "2") (pinfunction "2_2") (pintype "passive"))
      (node (ref "R4") (pin "1") (pinfunction "1_1") (pintype "passive"))
      (node (ref "R8") (pin "2") (pinfunction "2_2") (pintype "passive"))
      (node (ref "R9") (pin "2") (pinfunction "2_2") (pintype "passive"))
      (node (ref "SW3") (pin "3") (pinfunction "3_3") (pintype "passive"))
      (node (ref "SW3") (pin "4") (pinfunction "4_4") (pintype "passive"))
      (node (ref "T6") (pin "1") (pinfunction "Pad_1") (pintype "passive"))
      (node (ref "T7") (pin "1") (pinfunction "Pad_1") (pintype "passive"))
      (node (ref "U1") (pin "2") (pinfunction "GND_2") (pintype "power_in"))
      (node (ref "U2") (pin "2") (pinfunction "GND_2") (pintype "power_in"))
      (node (ref "U3") (pin "4") (pinfunction "VSS/VSSA_4") (pintype "power_in"))
      (node (ref "U4") (pin "2") (pintype "input"))
      (node (ref "U5") (pin "1") (pintype "input"))
      (node (ref "Y1") (pin "2") (pinfunction "GND_2") (pintype "power_in"))
      (node (ref "Y1") (pin "4") (pinfunction "GND_4") (pintype "power_in"))
    )
    (net (code "36") (name "Net-(C24-Pad1)") (class "Default")
      (node (ref "C24") (pin "1") (pinfunction "1_1") (pintype "passive"))
      (node (ref "U5") (pin "4") (pintype "bidirectional"))
    )
    (net (code "37") (name "Net-(C25-Pad1)") (class "Default")
      (node (ref "C25") (pin "1") (pinfunction "1_1") (pintype "passive"))
      (node (ref "U5") (pin "13") (pintype "bidirectional"))
    )
    (net (code "38") (name "Net-(D1-A)") (class "Default")
      (node (ref "D1") (pin "2") (pinfunction "A_2") (pintype "passive"))
      (node (ref "R6") (pin "2") (pinfunction "2_2") (pintype "passive"))
    )
    (net (code "39") (name "Net-(D2-A)") (class "Default")
      (node (ref "D2") (pin "2") (pinfunction "A_2") (pintype "passive"))
      (node (ref "R5") (pin "2") (pinfunction "2_2") (pintype "passive"))
    )
    (net (code "40") (name "Net-(D3-A)") (class "Default")
      (node (ref "D3") (pin "2") (pinfunction "A_2") (pintype "passive"))
      (node (ref "R7") (pin "2") (pinfunction "2_2") (pintype "passive"))
    )
    (net (code "41") (name "Net-(D4-A)") (class "Default")
      (node (ref "D4") (pin "2") (pinfunction "A_2") (pintype "passive"))
      (node (ref "J7") (pin "A4-B9") (pinfunction "VBUS_A4-B9") (pintype "power_in"))
      (node (ref "J7") (pin "B4-A9") (pinfunction "VBUS_B4-A9") (pintype "power_in"))
    )
    (net (code "42") (name "Net-(D5-C)") (class "Default")
      (node (ref "D5") (pin "1") (pinfunction "C_1") (pintype "passive"))
      (node (ref "R12") (pin "2") (pinfunction "2_2") (pintype "passive"))
    )
    (net (code "43") (name "Net-(D6-C)") (class "Default")
      (node (ref "D6") (pin "1") (pinfunction "C_1") (pintype "passive"))
      (node (ref "R13") (pin "2") (pinfunction "2_2") (pintype "passive"))
    )
    (net (code "44") (name "Net-(J7A-CC1)") (class "Default")
      (node (ref "J7") (pin "A5") (pinfunction "CC1_A5") (pintype "passive"))
      (node (ref "R8") (pin "1") (pinfunction "1_1") (pintype "passive"))
    )
    (net (code "45") (name "Net-(J7A-CC2)") (class "Default")
      (node (ref "J7") (pin "B5") (pinfunction "CC2_B5") (pintype "passive"))
      (node (ref "R9") (pin "1") (pinfunction "1_1") (pintype "passive"))
    )
    (net (code "46") (name "Net-(L1-DOUT)") (class "Default")
      (node (ref "L1") (pin "2") (pinfunction "DOUT_2") (pintype "output"))
      (node (ref "L2") (pin "4") (pinfunction "DIN_4") (pintype "input"))
    )
    (net (code "47") (name "Net-(U1-ADD0)") (class "Default")
      (node (ref "R1") (pin "1") (pinfunction "1_1") (pintype "passive"))
      (node (ref "R2") (pin "1") (pinfunction "1_1") (pintype "passive"))
      (node (ref "U1") (pin "4") (pinfunction "ADD0_4") (pintype "input"))
    )
    (net (code "48") (name "Net-(U1-ALERT)") (class "Default")
      (node (ref "T1") (pin "1") (pinfunction "Pad_1") (pintype "passive"))
      (node (ref "U1") (pin "3") (pinfunction "ALERT_3") (pintype "output"))
    )
    (net (code "49") (name "unconnected-(J7A-SBU1-PadA8)") (class "Default")
      (node (ref "J7") (pin "A8") (pinfunction "SBU1_A8") (pintype "passive+no_connect"))
    )
    (net (code "50") (name "unconnected-(J7A-SBU2-PadB8)") (class "Default")
      (node (ref "J7") (pin "B8") (pinfunction "SBU2_B8") (pintype "passive+no_connect"))
    )
    (net (code "51") (name "unconnected-(U2-NC-Pad4)") (class "Default")
      (node (ref "U2") (pin "4") (pinfunction "NC_4") (pintype "passive+no_connect"))
    )
    (net (code "52") (name "unconnected-(U5-Pad7)") (class "Default")
      (node (ref "U5") (pin "7") (pintype "input+no_connect"))
    )
    (net (code "53") (name "unconnected-(U5-Pad8)") (class "Default")
      (node (ref "U5") (pin "8") (pintype "bidirectional+no_connect"))
    )
    (net (code "54") (name "unconnected-(U5-Pad9)") (class "Default")
      (node (ref "U5") (pin "9") (pintype "bidirectional+no_connect"))
    )
    (net (code "55") (name "unconnected-(U5-Pad10)") (class "Default")
      (node (ref "U5") (pin "10") (pintype "bidirectional+no_connect"))
    )
    (net (code "56") (name "unconnected-(U5-Pad11)") (class "Default")
      (node (ref "U5") (pin "11") (pintype "bidirectional+no_connect"))
    )
    (net (code "57") (name "unconnected-(U5-Pad12)") (class "Default")
      (node (ref "U5") (pin "12") (pintype "bidirectional+no_connect"))
    )
    (net (code "58") (name "unconnected-(U5-Pad14)") (class "Default")
      (node (ref "U5") (pin "14") (pintype "bidirectional+no_connect"))
    )
    (net (code "59") (name "unconnected-(U5-Pad15)") (class "Default")
      (node (ref "U5") (pin "15") (pintype "bidirectional+no_connect"))
    )
  )
)
